# schema3.net
KiCad netlist of a schematic drawn in Altium Designer
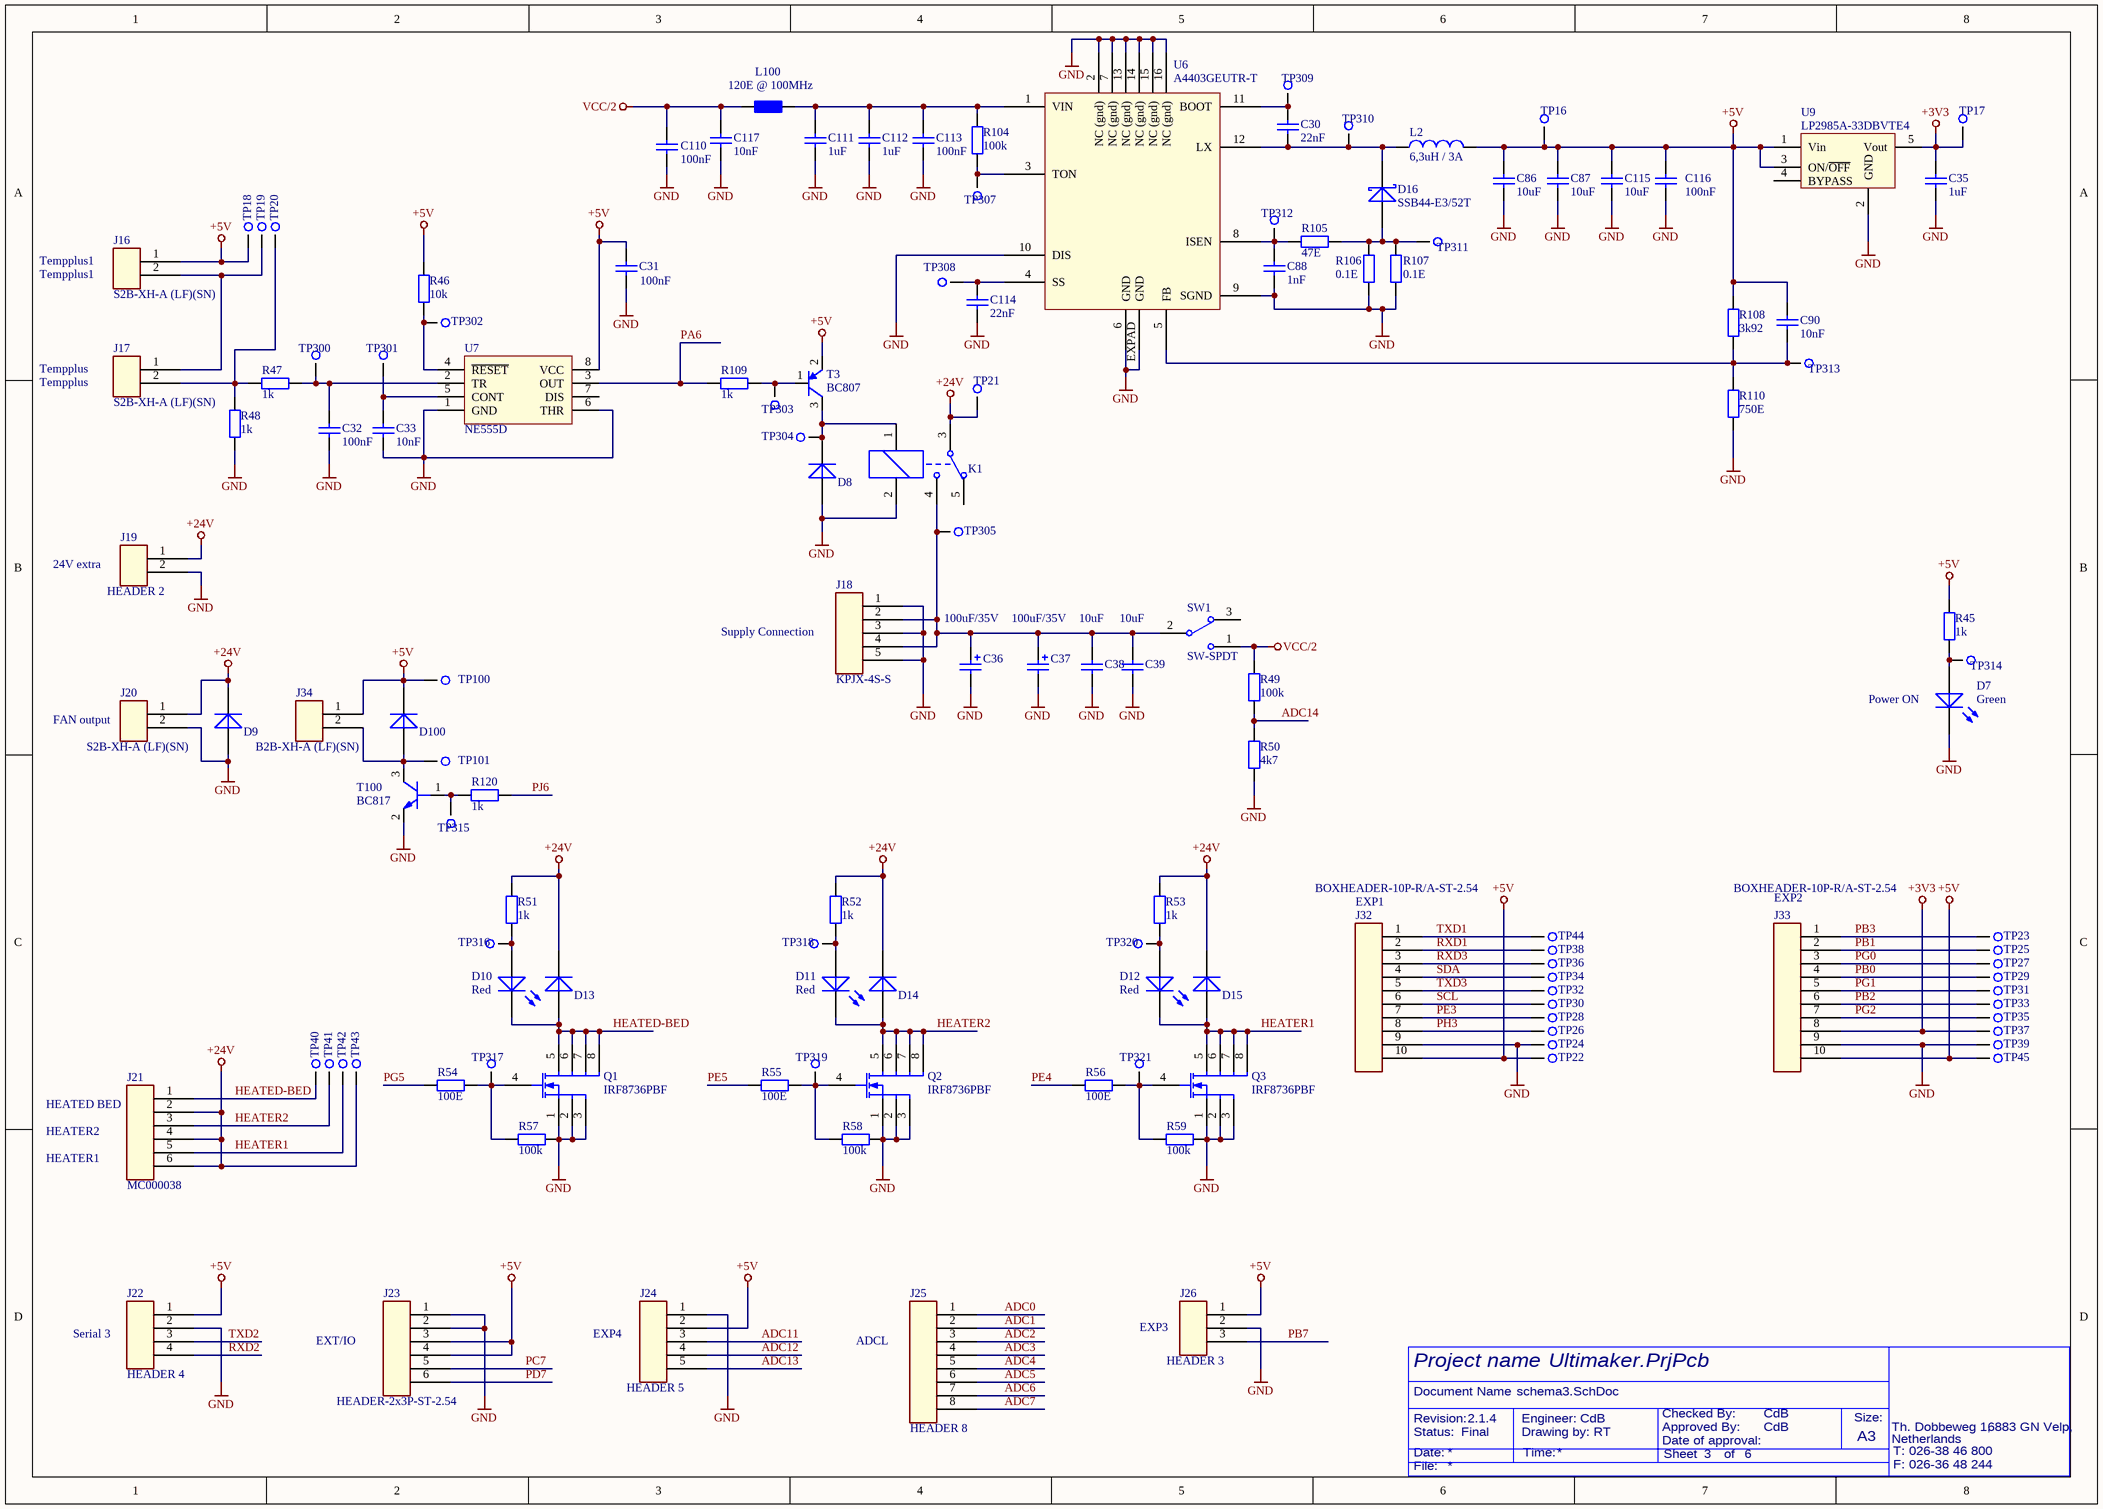
[diagram p0: schema3.SchDoc]

(export (version "E")
  (design (tool "Eeschema 10.0.6"))
  (components
    (comp (ref "C30")
      (value "22nF")
      (footprint "C0603")
      (description "RO X7R 22nF 10% 0603 50V CC0603KRX7R9BB223")
      (libsource (lib "Database_Faber") (part "Capacitor"))
    )
    (comp (ref "C31")
      (value "100nF")
      (footprint "C0603")
      (description "RO X7R 100nF 10% 50V 0603")
      (libsource (lib "Database_Faber") (part "Capacitor"))
    )
    (comp (ref "C32")
      (value "100nF")
      (footprint "C0603")
      (description "RO X7R 100nF 10% 50V 0603")
      (libsource (lib "Database_Faber") (part "Capacitor"))
    )
    (comp (ref "C33")
      (value "10nF")
      (footprint "C0603")
      (description "RO X7R 10nF 10% 50V 0603")
      (libsource (lib "Database_Faber") (part "Capacitor"))
    )
    (comp (ref "C35")
      (value "1uF")
      (footprint "C0603")
      (description "RO X5R 1uF 10% 10V 0603")
      (libsource (lib "Database_Faber") (part "Capacitor"))
    )
    (comp (ref "C36")
      (value "100uF/35V")
      (footprint "ELCO Case D")
      (description "RO ELCO 100uF 20% 35V CASE-D EEEFP PAN")
      (libsource (lib "Database_Faber") (part "Capacitor Polarity"))
    )
    (comp (ref "C37")
      (value "100uF/35V")
      (footprint "ELCO Case D")
      (description "RO ELCO 100uF 20% 35V CASE-D EEEFP PAN")
      (libsource (lib "Database_Faber") (part "Capacitor Polarity"))
    )
    (comp (ref "C38")
      (value "10uF")
      (footprint "C1206")
      (description "RO X5R 10UF 10% 35V 1206")
      (libsource (lib "Database_Faber") (part "Capacitor"))
    )
    (comp (ref "C39")
      (value "10uF")
      (footprint "C1206")
      (description "RO X5R 10UF 10% 35V 1206")
      (libsource (lib "Database_Faber") (part "Capacitor"))
    )
    (comp (ref "C86")
      (value "10uF")
      (footprint "C0805")
      (description "6R3R15X106KV4E - MLCC, 0805, X5R, 6.3V, 10UF")
      (fields (field (name "MFG") "JOHANSON DIELECTRICS"))
      (libsource (lib "Database_Faber") (part "Capacitor"))
    )
    (comp (ref "C87")
      (value "10uF")
      (footprint "C0805")
      (description "6R3R15X106KV4E - MLCC, 0805, X5R, 6.3V, 10UF")
      (fields (field (name "MFG") "JOHANSON DIELECTRICS"))
      (libsource (lib "Database_Faber") (part "Capacitor"))
    )
    (comp (ref "C88")
      (value "1nF")
      (footprint "C0603")
      (description "RO C0G 1nF 5% 50V 0603")
      (libsource (lib "Database_Faber") (part "Capacitor"))
    )
    (comp (ref "C90")
      (value "10nF")
      (footprint "C0603")
      (description "RO X7R 10nF 10% 50V 0603")
      (libsource (lib "Database_Faber") (part "Capacitor"))
    )
    (comp (ref "C110")
      (value "100nF")
      (footprint "Ultimaker:C0603")
      (description "RO X7R 100nF 10% 50V 0603")
      (libsource (lib "Database_Faber") (part "Capacitor"))
    )
    (comp (ref "C111")
      (value "1uF")
      (footprint "Ultimaker:C1206")
      (description "X7R 1uF 10% 50V 1206 GRM31")
      (libsource (lib "Ultimaker") (part "Capacitor_1_1"))
    )
    (comp (ref "C112")
      (value "1uF")
      (footprint "Ultimaker:C1206")
      (description "X7R 1uF 10% 50V 1206 GRM31")
      (libsource (lib "Ultimaker") (part "Capacitor_1_1"))
    )
    (comp (ref "C113")
      (value "100nF")
      (footprint "Ultimaker:C0603")
      (description "RO X7R 100nF 10% 50V 0603")
      (libsource (lib "Database_Faber") (part "Capacitor"))
    )
    (comp (ref "C114")
      (value "22nF")
      (footprint "Ultimaker:C0603")
      (description "RO X7R 22nF 10% 0603 50V CC0603KRX7R9BB223")
      (libsource (lib "Database_Faber") (part "Capacitor"))
    )
    (comp (ref "C115")
      (value "10uF")
      (footprint "Ultimaker:C0805")
      (description "6R3R15X106KV4E - MLCC, 0805, X5R, 6.3V, 10UF")
      (fields (field (name "MFG") "JOHANSON DIELECTRICS"))
      (libsource (lib "Database_Faber") (part "Capacitor"))
    )
    (comp (ref "C116")
      (value "100nF")
      (footprint "Ultimaker:C0603")
      (description "RO X7R 100nF 10% 50V 0603")
      (libsource (lib "Database_Faber") (part "Capacitor"))
    )
    (comp (ref "C117")
      (value "10nF")
      (footprint "Ultimaker:C0603")
      (description "RO X7R 10nF 10% 50V 0603")
      (libsource (lib "Database_Faber") (part "Capacitor"))
    )
    (comp (ref "D7")
      (value "Green")
      (footprint "LED0805-GREEN")
      (description "RO LED GROEN HSMG-C170 0805 AVAGO")
      (fields (field (name "MFG") "AVAGO"))
      (libsource (lib "Database_Faber") (part "LED"))
    )
    (comp (ref "D8")
      (value "S1G")
      (footprint "DO214AC (SMA)")
      (description "RO DIODE S1G DO-214AC")
      (libsource (lib "") (part "Diode_1"))
    )
    (comp (ref "D9")
      (value "S1G")
      (footprint "DO214AC (SMA)")
      (description "RO DIODE S1G DO-214AC")
      (libsource (lib "") (part "Diode_1"))
    )
    (comp (ref "D10")
      (value "Red")
      (footprint "LED0805-RED")
      (description "RO LED ROOD HSMH-C170 0805 AVAGO")
      (fields (field (name "MFG") "AVAGO"))
      (libsource (lib "Database_Faber") (part "LED"))
    )
    (comp (ref "D11")
      (value "Red")
      (footprint "LED0805-RED")
      (description "RO LED ROOD HSMH-C170 0805 AVAGO")
      (fields (field (name "MFG") "AVAGO"))
      (libsource (lib "Database_Faber") (part "LED"))
    )
    (comp (ref "D12")
      (value "Red")
      (footprint "LED0805-RED")
      (description "RO LED ROOD HSMH-C170 0805 AVAGO")
      (fields (field (name "MFG") "AVAGO"))
      (libsource (lib "Database_Faber") (part "LED"))
    )
    (comp (ref "D13")
      (value "S1G")
      (footprint "DO214AC (SMA)")
      (description "RO DIODE S1G DO-214AC")
      (libsource (lib "") (part "Diode_1"))
    )
    (comp (ref "D14")
      (value "S1G")
      (footprint "DO214AC (SMA)")
      (description "RO DIODE S1G DO-214AC")
      (libsource (lib "") (part "Diode_1"))
    )
    (comp (ref "D15")
      (value "S1G")
      (footprint "DO214AC (SMA)")
      (description "RO DIODE S1G DO-214AC")
      (libsource (lib "") (part "Diode_1"))
    )
    (comp (ref "D16")
      (value "SSB44-E3/52T")
      (footprint "DO214AA (SMB)")
      (description "RO DIODE SSB44-E3/52T SMB VISHAY")
      (fields (field (name "MFG") "VISHAY"))
      (libsource (lib "Database_Faber") (part "Schottky"))
    )
    (comp (ref "D100")
      (value "S1G")
      (footprint "Ultimaker:DO214AC (SMA)")
      (description "RO DIODE S1G DO-214AC")
      (libsource (lib "Database_Faber") (part "Diode"))
    )
    (comp (ref "J16")
      (value "S2B-XH-A (LF)(SN)")
      (footprint "S2B-XH-A (LF)(SN)")
      (description "RO CONN PR 2p HKS S2B-XH-A (LF)(SN) JST")
      (fields (field (name "MFG") "JST (JAPAN SOLDERLESS TERMINALS)"))
      (libsource (lib "Database_Faber") (part "HEADER 2"))
    )
    (comp (ref "J17")
      (value "S2B-XH-A (LF)(SN)")
      (footprint "S2B-XH-A (LF)(SN)")
      (description "RO CONN PR 2p HKS S2B-XH-A (LF)(SN) JST")
      (fields (field (name "MFG") "JST (JAPAN SOLDERLESS TERMINALS)"))
      (libsource (lib "Database_Faber") (part "HEADER 2"))
    )
    (comp (ref "J18")
      (value "KPJX-4S-S")
      (footprint "KPJX-4S-S")
      (description "RO CONN PR KPJX-4S-S KYCON")
      (fields (field (name "MFG") "KYCON"))
      (libsource (lib "Database_Faber") (part "HEADER 5"))
    )
    (comp (ref "J19")
      (value "HEADER 2")
      (footprint "HEADER-1x2P-ST-2.54")
      (description "HEADER-1x2P-ST-2.54")
      (libsource (lib "Database_Faber") (part "HEADER 2"))
    )
    (comp (ref "J20")
      (value "S2B-XH-A (LF)(SN)")
      (footprint "S2B-XH-A (LF)(SN)")
      (description "RO CONN PR 2p HKS S2B-XH-A (LF)(SN) JST")
      (fields (field (name "MFG") "JST (JAPAN SOLDERLESS TERMINALS)"))
      (libsource (lib "Database_Faber") (part "HEADER 2"))
    )
    (comp (ref "J21")
      (value "MC000038")
      (footprint "MC000038")
      (description "RO CONN PR 6p MC000038 MULTICOMP")
      (fields (field (name "MFG") "MULTICOMP"))
      (libsource (lib "Database_Faber") (part "HEADER 6"))
    )
    (comp (ref "J22")
      (value "HEADER 4")
      (footprint "HEADER-1x4P-ST-2.54")
      (description "HEADER-1x4P-ST-2.54")
      (libsource (lib "Database_Faber") (part "HEADER 4"))
    )
    (comp (ref "J23")
      (value "HEADER-2x3P-ST-2.54")
      (footprint "HEADER-2x3P-ST-2.54")
      (description "RO CONN PR HDR 2X3P H4B-06DS-0000 INT")
      (libsource (lib "Database_Faber") (part "HEADER 6"))
    )
    (comp (ref "J24")
      (value "HEADER 5")
      (footprint "HEADER-1x5P-ST-2.54")
      (description "HEADER-1x5P-ST-2.54")
      (libsource (lib "Database_Faber") (part "HEADER 5"))
    )
    (comp (ref "J25")
      (value "HEADER 8")
      (footprint "HEADER-1x8P-ST-2.54")
      (description "HEADER-1x8P-ST-2.54")
      (libsource (lib "Database_Faber") (part "HEADER 8"))
    )
    (comp (ref "J26")
      (value "HEADER 3")
      (footprint "HEADER-1x3P-ST-2.54")
      (description "HEADER-1x3P-ST-2.54")
      (libsource (lib "Database_Faber") (part "HEADER 3"))
    )
    (comp (ref "J32")
      (value "BOXHEADER-10P-R/A-ST-2.54")
      (footprint "BOXHEADER-10P-R/A-ST-2.54")
      (description "RO CONN PR HDR BOX 10p HKS 61201021721 WUERTH")
      (libsource (lib "Database_Faber") (part "HEADER 10"))
    )
    (comp (ref "J33")
      (value "BOXHEADER-10P-R/A-ST-2.54")
      (footprint "BOXHEADER-10P-R/A-ST-2.54")
      (description "RO CONN PR HDR BOX 10p HKS 61201021721 WUERTH")
      (libsource (lib "Database_Faber") (part "HEADER 10"))
    )
    (comp (ref "J34")
      (value "B2B-XH-A (LF)(SN)")
      (footprint "B2B-XH-A (LF)(SN)")
      (description "CONN PR 2p B2B-XH-A JST")
      (fields (field (name "MFG") "JST (JAPAN SOLDERLESS TERMINALS)"))
      (libsource (lib "Ultimaker") (part "HEADER 2_3"))
    )
    (comp (ref "K1")
      (value "Relay-SPDT")
      (footprint "HRS4-S")
      (description "RO REL 5V HRS4-S DC5V MULTICOMP")
      (fields (field (name "MFG") "MULTICOMP"))
      (libsource (lib "Database_Faber") (part "Relay-SPDT"))
    )
    (comp (ref "L2")
      (value "6,3uH / 3A")
      (footprint "NRS6045")
      (description "RO SPOEL 6,3uH 20% NRS6045T 6R3MMGK TAIYO YUDEN")
      (fields (field (name "MFG") "TAIYO YUDEN"))
      (libsource (lib "Database_Faber") (part "Inductor"))
    )
    (comp (ref "L100")
      (value "120E @ 100MHz")
      (footprint "Ultimaker:R0603")
      (description "FERRIET BLM18PG121SN1D 0603 MURATA")
      (fields (field (name "MFG") "Murata"))
      (libsource (lib "Ultimaker") (part "Ferriet Bead 120E"))
    )
    (comp (ref "Q1")
      (value "IRF8736PBF")
      (footprint "SOIC127P600X175-8N (SO8)")
      (description "IRF8736PBF - MOSFET, N SO-8")
      (fields (field (name "MFG") "INTERNATIONAL RECTIFIER"))
      (libsource (lib "Database_Faber") (part "MOSFET-N-SO8"))
    )
    (comp (ref "Q2")
      (value "IRF8736PBF")
      (footprint "SOIC127P600X175-8N (SO8)")
      (description "IRF8736PBF - MOSFET, N SO-8")
      (fields (field (name "MFG") "INTERNATIONAL RECTIFIER"))
      (libsource (lib "Database_Faber") (part "MOSFET-N-SO8"))
    )
    (comp (ref "Q3")
      (value "IRF8736PBF")
      (footprint "SOIC127P600X175-8N (SO8)")
      (description "IRF8736PBF - MOSFET, N SO-8")
      (fields (field (name "MFG") "INTERNATIONAL RECTIFIER"))
      (libsource (lib "Database_Faber") (part "MOSFET-N-SO8"))
    )
    (comp (ref "R45")
      (value "1k")
      (footprint "R0603")
      (description "RO RES 1k0 1% 0,1W  0603")
      (libsource (lib "Database_Faber") (part "Resistor"))
    )
    (comp (ref "R46")
      (value "10k")
      (footprint "R0603")
      (description "RO RES 10k0 1% 0,063W  0603")
      (libsource (lib "Database_Faber") (part "Resistor"))
    )
    (comp (ref "R47")
      (value "1k")
      (footprint "R0603")
      (description "RO RES 1k0 1% 0,1W  0603")
      (libsource (lib "") (part "Resistor_1"))
    )
    (comp (ref "R48")
      (value "1k")
      (footprint "R0603")
      (description "RO RES 1k0 1% 0,1W  0603")
      (libsource (lib "Database_Faber") (part "Resistor"))
    )
    (comp (ref "R49")
      (value "100k")
      (footprint "R0603")
      (description "RO RES 100k0 1% 0,063W  0603")
      (libsource (lib "Database_Faber") (part "Resistor"))
    )
    (comp (ref "R50")
      (value "4k7")
      (footprint "R0603")
      (description "RO RES 4k70 1% 0,063W  0603")
      (libsource (lib "Database_Faber") (part "Resistor"))
    )
    (comp (ref "R51")
      (value "1k")
      (footprint "R0603")
      (description "RO RES 1k0 1% 0,1W  0603")
      (libsource (lib "Database_Faber") (part "Resistor"))
    )
    (comp (ref "R52")
      (value "1k")
      (footprint "R0603")
      (description "RO RES 1k0 1% 0,1W  0603")
      (libsource (lib "Database_Faber") (part "Resistor"))
    )
    (comp (ref "R53")
      (value "1k")
      (footprint "R0603")
      (description "RO RES 1k0 1% 0,1W  0603")
      (libsource (lib "Database_Faber") (part "Resistor"))
    )
    (comp (ref "R54")
      (value "100E")
      (footprint "R0603")
      (description "RO RES 100E 1% 0,063W  0603")
      (libsource (lib "") (part "Resistor_1"))
    )
    (comp (ref "R55")
      (value "100E")
      (footprint "R0603")
      (description "RO RES 100E 1% 0,063W  0603")
      (libsource (lib "") (part "Resistor_1"))
    )
    (comp (ref "R56")
      (value "100E")
      (footprint "R0603")
      (description "RO RES 100E 1% 0,063W  0603")
      (libsource (lib "") (part "Resistor_1"))
    )
    (comp (ref "R57")
      (value "100k")
      (footprint "R0603")
      (description "RO RES 100k0 1% 0,063W  0603")
      (libsource (lib "") (part "Resistor_1"))
    )
    (comp (ref "R58")
      (value "100k")
      (footprint "R0603")
      (description "RO RES 100k0 1% 0,063W  0603")
      (libsource (lib "") (part "Resistor_1"))
    )
    (comp (ref "R59")
      (value "100k")
      (footprint "R0603")
      (description "RO RES 100k0 1% 0,063W  0603")
      (libsource (lib "") (part "Resistor_1"))
    )
    (comp (ref "R104")
      (value "100k")
      (footprint "R0603")
      (description "RO RES 100k0 1% 0,063W  0603")
      (libsource (lib "Database_Faber") (part "Resistor"))
    )
    (comp (ref "R105")
      (value "47E")
      (footprint "R0603")
      (description "RO RES 47E 1% 0,063W 0603")
      (libsource (lib "") (part "Resistor_1"))
    )
    (comp (ref "R106")
      (value "0.1E")
      (footprint "Ultimaker:R0805")
      (description "RES 0E10 1% 0,125W 0805")
      (libsource (lib "Database_Faber") (part "Resistor"))
    )
    (comp (ref "R107")
      (value "0.1E")
      (footprint "Ultimaker:R0805")
      (description "RES 0E10 1% 0,125W 0805")
      (libsource (lib "Database_Faber") (part "Resistor"))
    )
    (comp (ref "R108")
      (value "3k92")
      (footprint "R0603")
      (description "RO RES 3k92 1% 0.063W 0603")
      (libsource (lib "Database_Faber") (part "Resistor"))
    )
    (comp (ref "R109")
      (value "1k")
      (footprint "R0603")
      (description "RO RES 1k0 1% 0,1W  0603")
      (libsource (lib "") (part "Resistor_1"))
    )
    (comp (ref "R110")
      (value "750E")
      (footprint "R0603")
      (description "RO RES 750E 1% 0,063W 0603")
      (libsource (lib "Database_Faber") (part "Resistor"))
    )
    (comp (ref "R120")
      (value "1k")
      (footprint "Ultimaker:R0603")
      (description "RO RES 1k0 1% 0,1W  0603")
      (libsource (lib "") (part "Resistor_2"))
    )
    (comp (ref "SW1")
      (value "SW-SPDT")
      (footprint "RS 734-6918")
      (description "Rocker switch,SPDT,on-none-on,RA,snap-in")
      (fields (field (name "MFG") "RS Components"))
      (libsource (lib "Database_Faber") (part "SW-SPDT"))
    )
    (comp (ref "T3")
      (value "BC807")
      (footprint "SOT23")
      (description "RO TRANS BC807-40  SOT-23")
      (libsource (lib "Database_Faber") (part "Transistor PNP"))
    )
    (comp (ref "T100")
      (value "BC817")
      (footprint "Ultimaker:SOT23")
      (description "RO TRANS BC817-25  SOT-23")
      (libsource (lib "Database_Faber") (part "Transistor NPN"))
    )
    (comp (ref "TP16")
      (value "Testpoint")
      (footprint "Testpoint")
      (libsource (lib "Database_Faber") (part "Testpoint"))
    )
    (comp (ref "TP17")
      (value "Testpoint")
      (footprint "Testpoint")
      (libsource (lib "Database_Faber") (part "Testpoint"))
    )
    (comp (ref "TP18")
      (value "Testpoint")
      (footprint "Testpoint")
      (libsource (lib "Database_Faber") (part "Testpoint"))
    )
    (comp (ref "TP19")
      (value "Testpoint")
      (footprint "Testpoint")
      (libsource (lib "Database_Faber") (part "Testpoint"))
    )
    (comp (ref "TP20")
      (value "Testpoint")
      (footprint "Testpoint")
      (libsource (lib "Database_Faber") (part "Testpoint"))
    )
    (comp (ref "TP21")
      (value "Testpoint")
      (footprint "Testpoint")
      (libsource (lib "Database_Faber") (part "Testpoint"))
    )
    (comp (ref "TP22")
      (value "Testpoint")
      (footprint "Testpoint")
      (libsource (lib "Database_Faber") (part "Testpoint"))
    )
    (comp (ref "TP23")
      (value "Testpoint")
      (footprint "Testpoint")
      (libsource (lib "Database_Faber") (part "Testpoint"))
    )
    (comp (ref "TP24")
      (value "Testpoint")
      (footprint "Testpoint")
      (libsource (lib "Database_Faber") (part "Testpoint"))
    )
    (comp (ref "TP25")
      (value "Testpoint")
      (footprint "Testpoint")
      (libsource (lib "Database_Faber") (part "Testpoint"))
    )
    (comp (ref "TP26")
      (value "Testpoint")
      (footprint "Testpoint")
      (libsource (lib "Database_Faber") (part "Testpoint"))
    )
    (comp (ref "TP27")
      (value "Testpoint")
      (footprint "Testpoint")
      (libsource (lib "Database_Faber") (part "Testpoint"))
    )
    (comp (ref "TP28")
      (value "Testpoint")
      (footprint "Testpoint")
      (libsource (lib "Database_Faber") (part "Testpoint"))
    )
    (comp (ref "TP29")
      (value "Testpoint")
      (footprint "Testpoint")
      (libsource (lib "Database_Faber") (part "Testpoint"))
    )
    (comp (ref "TP30")
      (value "Testpoint")
      (footprint "Testpoint")
      (libsource (lib "Database_Faber") (part "Testpoint"))
    )
    (comp (ref "TP31")
      (value "Testpoint")
      (footprint "Testpoint")
      (libsource (lib "Database_Faber") (part "Testpoint"))
    )
    (comp (ref "TP32")
      (value "Testpoint")
      (footprint "Testpoint")
      (libsource (lib "Database_Faber") (part "Testpoint"))
    )
    (comp (ref "TP33")
      (value "Testpoint")
      (footprint "Testpoint")
      (libsource (lib "Database_Faber") (part "Testpoint"))
    )
    (comp (ref "TP34")
      (value "Testpoint")
      (footprint "Testpoint")
      (libsource (lib "Database_Faber") (part "Testpoint"))
    )
    (comp (ref "TP35")
      (value "Testpoint")
      (footprint "Testpoint")
      (libsource (lib "Database_Faber") (part "Testpoint"))
    )
    (comp (ref "TP36")
      (value "Testpoint")
      (footprint "Testpoint")
      (libsource (lib "Database_Faber") (part "Testpoint"))
    )
    (comp (ref "TP37")
      (value "Testpoint")
      (footprint "Testpoint")
      (libsource (lib "Database_Faber") (part "Testpoint"))
    )
    (comp (ref "TP38")
      (value "Testpoint")
      (footprint "Testpoint")
      (libsource (lib "Database_Faber") (part "Testpoint"))
    )
    (comp (ref "TP39")
      (value "Testpoint")
      (footprint "Testpoint")
      (libsource (lib "Database_Faber") (part "Testpoint"))
    )
    (comp (ref "TP40")
      (value "Testpoint")
      (footprint "Testpoint")
      (libsource (lib "Database_Faber") (part "Testpoint"))
    )
    (comp (ref "TP41")
      (value "Testpoint")
      (footprint "Testpoint")
      (libsource (lib "Database_Faber") (part "Testpoint"))
    )
    (comp (ref "TP42")
      (value "Testpoint")
      (footprint "Testpoint")
      (libsource (lib "Database_Faber") (part "Testpoint"))
    )
    (comp (ref "TP43")
      (value "Testpoint")
      (footprint "Testpoint")
      (libsource (lib "Database_Faber") (part "Testpoint"))
    )
    (comp (ref "TP44")
      (value "Testpoint")
      (footprint "Testpoint")
      (libsource (lib "Database_Faber") (part "Testpoint"))
    )
    (comp (ref "TP45")
      (value "Testpoint")
      (footprint "Testpoint")
      (libsource (lib "Database_Faber") (part "Testpoint"))
    )
    (comp (ref "TP100")
      (value "Testpoint")
      (footprint "Ultimaker:Testpoint")
      (libsource (lib "Database_Faber") (part "Testpoint"))
    )
    (comp (ref "TP101")
      (value "Testpoint")
      (footprint "Ultimaker:Testpoint")
      (libsource (lib "Database_Faber") (part "Testpoint"))
    )
    (comp (ref "TP300")
      (value "Testpoint 1.6mm")
      (footprint "Testpoint 1.6mm")
      (libsource (lib "Ultimaker") (part "Testpoint 1.6mm"))
    )
    (comp (ref "TP301")
      (value "Testpoint 1.6mm")
      (footprint "Testpoint 1.6mm")
      (libsource (lib "Ultimaker") (part "Testpoint 1.6mm"))
    )
    (comp (ref "TP302")
      (value "Testpoint 1.6mm")
      (footprint "Testpoint 1.6mm")
      (libsource (lib "Ultimaker") (part "Testpoint 1.6mm"))
    )
    (comp (ref "TP303")
      (value "Testpoint 1.6mm")
      (footprint "Testpoint 1.6mm")
      (libsource (lib "Ultimaker") (part "Testpoint 1.6mm"))
    )
    (comp (ref "TP304")
      (value "Testpoint 1.6mm")
      (footprint "Testpoint 1.6mm")
      (libsource (lib "Ultimaker") (part "Testpoint 1.6mm"))
    )
    (comp (ref "TP305")
      (value "Testpoint 1.6mm")
      (footprint "Testpoint 1.6mm")
      (libsource (lib "Ultimaker") (part "Testpoint 1.6mm"))
    )
    (comp (ref "TP307")
      (value "Testpoint 1.6mm")
      (footprint "Testpoint 1.6mm")
      (libsource (lib "Ultimaker") (part "Testpoint 1.6mm"))
    )
    (comp (ref "TP308")
      (value "Testpoint 1.6mm")
      (footprint "Testpoint 1.6mm")
      (libsource (lib "Ultimaker") (part "Testpoint 1.6mm"))
    )
    (comp (ref "TP309")
      (value "Testpoint 1.6mm")
      (footprint "Testpoint 1.6mm")
      (libsource (lib "Ultimaker") (part "Testpoint 1.6mm"))
    )
    (comp (ref "TP310")
      (value "Testpoint 1.6mm")
      (footprint "Testpoint 1.6mm")
      (libsource (lib "Ultimaker") (part "Testpoint 1.6mm"))
    )
    (comp (ref "TP311")
      (value "Testpoint 1.6mm")
      (footprint "Testpoint 1.6mm")
      (libsource (lib "Ultimaker") (part "Testpoint 1.6mm"))
    )
    (comp (ref "TP312")
      (value "Testpoint 1.6mm")
      (footprint "Testpoint 1.6mm")
      (libsource (lib "Ultimaker") (part "Testpoint 1.6mm"))
    )
    (comp (ref "TP313")
      (value "Testpoint 1.6mm")
      (footprint "Testpoint 1.6mm")
      (libsource (lib "Ultimaker") (part "Testpoint 1.6mm"))
    )
    (comp (ref "TP314")
      (value "Testpoint 1.6mm")
      (footprint "Testpoint 1.6mm")
      (libsource (lib "Ultimaker") (part "Testpoint 1.6mm"))
    )
    (comp (ref "TP315")
      (value "Testpoint 1.6mm")
      (footprint "Testpoint 1.6mm")
      (libsource (lib "Ultimaker") (part "Testpoint 1.6mm"))
    )
    (comp (ref "TP316")
      (value "Testpoint 1.6mm")
      (footprint "Testpoint 1.6mm")
      (libsource (lib "Ultimaker") (part "Testpoint 1.6mm"))
    )
    (comp (ref "TP317")
      (value "Testpoint 1.6mm")
      (footprint "Testpoint 1.6mm")
      (libsource (lib "Ultimaker") (part "Testpoint 1.6mm"))
    )
    (comp (ref "TP318")
      (value "Testpoint 1.6mm")
      (footprint "Testpoint 1.6mm")
      (libsource (lib "Ultimaker") (part "Testpoint 1.6mm"))
    )
    (comp (ref "TP319")
      (value "Testpoint 1.6mm")
      (footprint "Testpoint 1.6mm")
      (libsource (lib "Ultimaker") (part "Testpoint 1.6mm"))
    )
    (comp (ref "TP320")
      (value "Testpoint 1.6mm")
      (footprint "Testpoint 1.6mm")
      (libsource (lib "Ultimaker") (part "Testpoint 1.6mm"))
    )
    (comp (ref "TP321")
      (value "Testpoint 1.6mm")
      (footprint "Testpoint 1.6mm")
      (libsource (lib "Ultimaker") (part "Testpoint 1.6mm"))
    )
    (comp (ref "U6")
      (value "A4403GEUTR-T")
      (footprint "QFN65P400X400X80-16N-EX")
      (description "RO IC A4403GEUTR-T QFN-16 ALLEGRO")
      (fields (field (name "MFG") "Allegro"))
      (libsource (lib "Database_Faber") (part "A4403GEUTR-T"))
    )
    (comp (ref "U7")
      (value "NE555D")
      (footprint "SOIC127P600X175-8N (SO8)")
      (description "RO IC NE555D SO-08 TI")
      (fields (field (name "MFG") "Texas Instruments"))
      (libsource (lib "Database_Faber") (part "NE555D"))
    )
    (comp (ref "U9")
      (value "LP2985A-33DBVTE4")
      (footprint "SOT95P280X145-5N (SOT23-5L)")
      (description "RO STABI LP2985A-33DBVTE4 SOT-23-5 TI")
      (fields (field (name "MFG") "Texas Instruments"))
      (libsource (lib "Database_Faber") (part "LP2985A-33DBVTE4"))
    )
  )
  (nets
    (net (code "1") (name "+3V3") (class "Default")
      (node (ref "C35") (pin "2") (pinfunction "2_2") (pintype "passive"))
      (node (ref "J33") (pin "8") (pinfunction "8_8") (pintype "passive"))
      (node (ref "TP17") (pin "1") (pinfunction "1_1") (pintype "passive"))
      (node (ref "TP37") (pin "1") (pinfunction "1_1") (pintype "passive"))
      (node (ref "U9") (pin "5") (pinfunction "Vout_5") (pintype "passive"))
    )
    (net (code "2") (name "+5V") (class "Default")
      (node (ref "C115") (pin "2") (pinfunction "2_2") (pintype "passive"))
      (node (ref "C116") (pin "2") (pinfunction "2_2") (pintype "passive"))
      (node (ref "C31") (pin "2") (pinfunction "2_2") (pintype "passive"))
      (node (ref "C86") (pin "2") (pinfunction "2_2") (pintype "passive"))
      (node (ref "C87") (pin "2") (pinfunction "2_2") (pintype "passive"))
      (node (ref "C90") (pin "2") (pinfunction "2_2") (pintype "passive"))
      (node (ref "D100") (pin "2") (pinfunction "K_2") (pintype "passive"))
      (node (ref "J16") (pin "1") (pinfunction "1_1") (pintype "passive"))
      (node (ref "J22") (pin "1") (pinfunction "1_1") (pintype "passive"))
      (node (ref "J23") (pin "3") (pinfunction "3_3") (pintype "passive"))
      (node (ref "J23") (pin "4") (pinfunction "4_4") (pintype "passive"))
      (node (ref "J24") (pin "2") (pinfunction "2_2") (pintype "passive"))
      (node (ref "J26") (pin "1") (pinfunction "1_1") (pintype "passive"))
      (node (ref "J32") (pin "10") (pinfunction "10_10") (pintype "passive"))
      (node (ref "J33") (pin "10") (pinfunction "10_10") (pintype "passive"))
      (node (ref "J34") (pin "1") (pinfunction "1_1") (pintype "passive"))
      (node (ref "L2") (pin "2") (pinfunction "2_2") (pintype "passive"))
      (node (ref "R108") (pin "2") (pinfunction "2_2") (pintype "passive"))
      (node (ref "R45") (pin "2") (pinfunction "2_2") (pintype "passive"))
      (node (ref "R46") (pin "2") (pinfunction "2_2") (pintype "passive"))
      (node (ref "T3") (pin "2") (pinfunction "E_2") (pintype "passive"))
      (node (ref "TP100") (pin "1") (pinfunction "1_1") (pintype "passive"))
      (node (ref "TP16") (pin "1") (pinfunction "1_1") (pintype "passive"))
      (node (ref "TP18") (pin "1") (pinfunction "1_1") (pintype "passive"))
      (node (ref "TP22") (pin "1") (pinfunction "1_1") (pintype "passive"))
      (node (ref "TP45") (pin "1") (pinfunction "1_1") (pintype "passive"))
      (node (ref "U7") (pin "8") (pinfunction "VCC_8") (pintype "passive"))
      (node (ref "U9") (pin "1") (pinfunction "Vin_1") (pintype "passive"))
      (node (ref "U9") (pin "3") (pinfunction "ON/~{OFF}_3") (pintype "passive"))
    )
    (net (code "3") (name "+24V") (class "Default")
      (node (ref "D13") (pin "2") (pinfunction "K_2") (pintype "passive"))
      (node (ref "D14") (pin "2") (pinfunction "K_2") (pintype "passive"))
      (node (ref "D15") (pin "2") (pinfunction "K_2") (pintype "passive"))
      (node (ref "D9") (pin "2") (pinfunction "K_2") (pintype "passive"))
      (node (ref "J19") (pin "1") (pinfunction "1_1") (pintype "passive"))
      (node (ref "J20") (pin "1") (pinfunction "1_1") (pintype "passive"))
      (node (ref "J21") (pin "2") (pinfunction "2_2") (pintype "passive"))
      (node (ref "J21") (pin "4") (pinfunction "4_4") (pintype "passive"))
      (node (ref "J21") (pin "6") (pinfunction "6_6") (pintype "passive"))
      (node (ref "K1") (pin "3") (pinfunction "3_3") (pintype "passive"))
      (node (ref "R51") (pin "2") (pinfunction "2_2") (pintype "passive"))
      (node (ref "R52") (pin "2") (pinfunction "2_2") (pintype "passive"))
      (node (ref "R53") (pin "2") (pinfunction "2_2") (pintype "passive"))
      (node (ref "TP21") (pin "1") (pinfunction "1_1") (pintype "passive"))
      (node (ref "TP43") (pin "1") (pinfunction "1_1") (pintype "passive"))
    )
    (net (code "4") (name "/ADC0") (class "Default")
      (node (ref "J25") (pin "1") (pinfunction "1_1") (pintype "passive"))
    )
    (net (code "5") (name "/ADC1") (class "Default")
      (node (ref "J25") (pin "2") (pinfunction "2_2") (pintype "passive"))
    )
    (net (code "6") (name "/ADC2") (class "Default")
      (node (ref "J25") (pin "3") (pinfunction "3_3") (pintype "passive"))
    )
    (net (code "7") (name "/ADC3") (class "Default")
      (node (ref "J25") (pin "4") (pinfunction "4_4") (pintype "passive"))
    )
    (net (code "8") (name "/ADC4") (class "Default")
      (node (ref "J25") (pin "5") (pinfunction "5_5") (pintype "passive"))
    )
    (net (code "9") (name "/ADC5") (class "Default")
      (node (ref "J25") (pin "6") (pinfunction "6_6") (pintype "passive"))
    )
    (net (code "10") (name "/ADC6") (class "Default")
      (node (ref "J25") (pin "7") (pinfunction "7_7") (pintype "passive"))
    )
    (net (code "11") (name "/ADC7") (class "Default")
      (node (ref "J25") (pin "8") (pinfunction "8_8") (pintype "passive"))
    )
    (net (code "12") (name "/ADC11") (class "Default")
      (node (ref "J24") (pin "3") (pinfunction "3_3") (pintype "passive"))
    )
    (net (code "13") (name "/ADC12") (class "Default")
      (node (ref "J24") (pin "4") (pinfunction "4_4") (pintype "passive"))
    )
    (net (code "14") (name "/ADC13") (class "Default")
      (node (ref "J24") (pin "5") (pinfunction "5_5") (pintype "passive"))
    )
    (net (code "15") (name "/ADC14") (class "Default")
      (node (ref "R49") (pin "1") (pinfunction "1_1") (pintype "passive"))
      (node (ref "R50") (pin "2") (pinfunction "2_2") (pintype "passive"))
    )
    (net (code "16") (name "/HEATED-BED") (class "Default")
      (node (ref "D10") (pin "2") (pinfunction "K_2") (pintype "passive"))
      (node (ref "D13") (pin "1") (pinfunction "A_1") (pintype "passive"))
      (node (ref "J21") (pin "1") (pinfunction "1_1") (pintype "passive"))
      (node (ref "Q1") (pin "5") (pinfunction "D_5") (pintype "passive"))
      (node (ref "Q1") (pin "6") (pinfunction "D_6") (pintype "passive"))
      (node (ref "Q1") (pin "7") (pinfunction "D_7") (pintype "passive"))
      (node (ref "Q1") (pin "8") (pinfunction "D_8") (pintype "passive"))
      (node (ref "TP40") (pin "1") (pinfunction "1_1") (pintype "passive"))
    )
    (net (code "17") (name "/HEATER1") (class "Default")
      (node (ref "D12") (pin "2") (pinfunction "K_2") (pintype "passive"))
      (node (ref "D15") (pin "1") (pinfunction "A_1") (pintype "passive"))
      (node (ref "J21") (pin "5") (pinfunction "5_5") (pintype "passive"))
      (node (ref "Q3") (pin "5") (pinfunction "D_5") (pintype "passive"))
      (node (ref "Q3") (pin "6") (pinfunction "D_6") (pintype "passive"))
      (node (ref "Q3") (pin "7") (pinfunction "D_7") (pintype "passive"))
      (node (ref "Q3") (pin "8") (pinfunction "D_8") (pintype "passive"))
      (node (ref "TP42") (pin "1") (pinfunction "1_1") (pintype "passive"))
    )
    (net (code "18") (name "/HEATER2") (class "Default")
      (node (ref "D11") (pin "2") (pinfunction "K_2") (pintype "passive"))
      (node (ref "D14") (pin "1") (pinfunction "A_1") (pintype "passive"))
      (node (ref "J21") (pin "3") (pinfunction "3_3") (pintype "passive"))
      (node (ref "Q2") (pin "5") (pinfunction "D_5") (pintype "passive"))
      (node (ref "Q2") (pin "6") (pinfunction "D_6") (pintype "passive"))
      (node (ref "Q2") (pin "7") (pinfunction "D_7") (pintype "passive"))
      (node (ref "Q2") (pin "8") (pinfunction "D_8") (pintype "passive"))
      (node (ref "TP41") (pin "1") (pinfunction "1_1") (pintype "passive"))
    )
    (net (code "19") (name "/PA6") (class "Default")
      (node (ref "R109") (pin "1") (pinfunction "1_1") (pintype "passive"))
      (node (ref "U7") (pin "3") (pinfunction "OUT_3") (pintype "passive"))
    )
    (net (code "20") (name "/PB0") (class "Default")
      (node (ref "J33") (pin "4") (pinfunction "4_4") (pintype "passive"))
      (node (ref "TP29") (pin "1") (pinfunction "1_1") (pintype "passive"))
    )
    (net (code "21") (name "/PB1") (class "Default")
      (node (ref "J33") (pin "2") (pinfunction "2_2") (pintype "passive"))
      (node (ref "TP25") (pin "1") (pinfunction "1_1") (pintype "passive"))
    )
    (net (code "22") (name "/PB2") (class "Default")
      (node (ref "J33") (pin "6") (pinfunction "6_6") (pintype "passive"))
      (node (ref "TP33") (pin "1") (pinfunction "1_1") (pintype "passive"))
    )
    (net (code "23") (name "/PB3") (class "Default")
      (node (ref "J33") (pin "1") (pinfunction "1_1") (pintype "passive"))
      (node (ref "TP23") (pin "1") (pinfunction "1_1") (pintype "passive"))
    )
    (net (code "24") (name "/PB7") (class "Default")
      (node (ref "J26") (pin "3") (pinfunction "3_3") (pintype "passive"))
    )
    (net (code "25") (name "/PC7") (class "Default")
      (node (ref "J23") (pin "5") (pinfunction "5_5") (pintype "passive"))
    )
    (net (code "26") (name "/PD7") (class "Default")
      (node (ref "J23") (pin "6") (pinfunction "6_6") (pintype "passive"))
    )
    (net (code "27") (name "/PE3") (class "Default")
      (node (ref "J32") (pin "7") (pinfunction "7_7") (pintype "passive"))
      (node (ref "TP28") (pin "1") (pinfunction "1_1") (pintype "passive"))
    )
    (net (code "28") (name "/PE4") (class "Default")
      (node (ref "R56") (pin "1") (pinfunction "1_1") (pintype "passive"))
    )
    (net (code "29") (name "/PE5") (class "Default")
      (node (ref "R55") (pin "1") (pinfunction "1_1") (pintype "passive"))
    )
    (net (code "30") (name "/PG0") (class "Default")
      (node (ref "J33") (pin "3") (pinfunction "3_3") (pintype "passive"))
      (node (ref "TP27") (pin "1") (pinfunction "1_1") (pintype "passive"))
    )
    (net (code "31") (name "/PG1") (class "Default")
      (node (ref "J33") (pin "5") (pinfunction "5_5") (pintype "passive"))
      (node (ref "TP31") (pin "1") (pinfunction "1_1") (pintype "passive"))
    )
    (net (code "32") (name "/PG2") (class "Default")
      (node (ref "J33") (pin "7") (pinfunction "7_7") (pintype "passive"))
      (node (ref "TP35") (pin "1") (pinfunction "1_1") (pintype "passive"))
    )
    (net (code "33") (name "/PG5") (class "Default")
      (node (ref "R54") (pin "1") (pinfunction "1_1") (pintype "passive"))
    )
    (net (code "34") (name "/PH3") (class "Default")
      (node (ref "J32") (pin "8") (pinfunction "8_8") (pintype "passive"))
      (node (ref "TP26") (pin "1") (pinfunction "1_1") (pintype "passive"))
    )
    (net (code "35") (name "/PJ6") (class "Default")
      (node (ref "R120") (pin "1") (pinfunction "1_1") (pintype "passive"))
    )
    (net (code "36") (name "/RXD1") (class "Default")
      (node (ref "J32") (pin "2") (pinfunction "2_2") (pintype "passive"))
      (node (ref "TP38") (pin "1") (pinfunction "1_1") (pintype "passive"))
    )
    (net (code "37") (name "/RXD2") (class "Default")
      (node (ref "J22") (pin "4") (pinfunction "4_4") (pintype "passive"))
    )
    (net (code "38") (name "/RXD3") (class "Default")
      (node (ref "J32") (pin "3") (pinfunction "3_3") (pintype "passive"))
      (node (ref "TP36") (pin "1") (pinfunction "1_1") (pintype "passive"))
    )
    (net (code "39") (name "/SCL") (class "Default")
      (node (ref "J32") (pin "6") (pinfunction "6_6") (pintype "passive"))
      (node (ref "TP30") (pin "1") (pinfunction "1_1") (pintype "passive"))
    )
    (net (code "40") (name "/SDA") (class "Default")
      (node (ref "J32") (pin "4") (pinfunction "4_4") (pintype "passive"))
      (node (ref "TP34") (pin "1") (pinfunction "1_1") (pintype "passive"))
    )
    (net (code "41") (name "/TXD1") (class "Default")
      (node (ref "J32") (pin "1") (pinfunction "1_1") (pintype "passive"))
      (node (ref "TP44") (pin "1") (pinfunction "1_1") (pintype "passive"))
    )
    (net (code "42") (name "/TXD2") (class "Default")
      (node (ref "J22") (pin "3") (pinfunction "3_3") (pintype "passive"))
    )
    (net (code "43") (name "/TXD3") (class "Default")
      (node (ref "J32") (pin "5") (pinfunction "5_5") (pintype "passive"))
      (node (ref "TP32") (pin "1") (pinfunction "1_1") (pintype "passive"))
    )
    (net (code "44") (name "GND") (class "Default")
      (node (ref "C110") (pin "1") (pinfunction "1_1") (pintype "passive"))
      (node (ref "C111") (pin "1") (pinfunction "1_1") (pintype "passive"))
      (node (ref "C112") (pin "1") (pinfunction "1_1") (pintype "passive"))
      (node (ref "C113") (pin "1") (pinfunction "1_1") (pintype "passive"))
      (node (ref "C114") (pin "1") (pinfunction "1_1") (pintype "passive"))
      (node (ref "C115") (pin "1") (pinfunction "1_1") (pintype "passive"))
      (node (ref "C116") (pin "1") (pinfunction "1_1") (pintype "passive"))
      (node (ref "C117") (pin "1") (pinfunction "1_1") (pintype "passive"))
      (node (ref "C31") (pin "1") (pinfunction "1_1") (pintype "passive"))
      (node (ref "C32") (pin "1") (pinfunction "1_1") (pintype "passive"))
      (node (ref "C33") (pin "1") (pinfunction "1_1") (pintype "passive"))
      (node (ref "C35") (pin "1") (pinfunction "1_1") (pintype "passive"))
      (node (ref "C36") (pin "2") (pinfunction "2_2") (pintype "passive"))
      (node (ref "C37") (pin "2") (pinfunction "2_2") (pintype "passive"))
      (node (ref "C38") (pin "1") (pinfunction "1_1") (pintype "passive"))
      (node (ref "C39") (pin "1") (pinfunction "1_1") (pintype "passive"))
      (node (ref "C86") (pin "1") (pinfunction "1_1") (pintype "passive"))
      (node (ref "C87") (pin "1") (pinfunction "1_1") (pintype "passive"))
      (node (ref "C88") (pin "1") (pinfunction "1_1") (pintype "passive"))
      (node (ref "D7") (pin "2") (pinfunction "K_2") (pintype "passive"))
      (node (ref "D8") (pin "1") (pinfunction "A_1") (pintype "passive"))
      (node (ref "D9") (pin "1") (pinfunction "A_1") (pintype "passive"))
      (node (ref "J18") (pin "1") (pinfunction "1_1") (pintype "passive"))
      (node (ref "J18") (pin "3") (pinfunction "3_3") (pintype "passive"))
      (node (ref "J18") (pin "5") (pinfunction "5_5") (pintype "passive"))
      (node (ref "J19") (pin "2") (pinfunction "2_2") (pintype "passive"))
      (node (ref "J20") (pin "2") (pinfunction "2_2") (pintype "passive"))
      (node (ref "J22") (pin "2") (pinfunction "2_2") (pintype "passive"))
      (node (ref "J23") (pin "1") (pinfunction "1_1") (pintype "passive"))
      (node (ref "J23") (pin "2") (pinfunction "2_2") (pintype "passive"))
      (node (ref "J24") (pin "1") (pinfunction "1_1") (pintype "passive"))
      (node (ref "J26") (pin "2") (pinfunction "2_2") (pintype "passive"))
      (node (ref "J32") (pin "9") (pinfunction "9_9") (pintype "passive"))
      (node (ref "J33") (pin "9") (pinfunction "9_9") (pintype "passive"))
      (node (ref "K1") (pin "2") (pinfunction "2_2") (pintype "passive"))
      (node (ref "Q1") (pin "1") (pinfunction "S_1") (pintype "passive"))
      (node (ref "Q1") (pin "2") (pinfunction "S_2") (pintype "passive"))
      (node (ref "Q1") (pin "3") (pinfunction "S_3") (pintype "passive"))
      (node (ref "Q2") (pin "1") (pinfunction "S_1") (pintype "passive"))
      (node (ref "Q2") (pin "2") (pinfunction "S_2") (pintype "passive"))
      (node (ref "Q2") (pin "3") (pinfunction "S_3") (pintype "passive"))
      (node (ref "Q3") (pin "1") (pinfunction "S_1") (pintype "passive"))
      (node (ref "Q3") (pin "2") (pinfunction "S_2") (pintype "passive"))
      (node (ref "Q3") (pin "3") (pinfunction "S_3") (pintype "passive"))
      (node (ref "R106") (pin "1") (pinfunction "1_1") (pintype "passive"))
      (node (ref "R107") (pin "1") (pinfunction "1_1") (pintype "passive"))
      (node (ref "R110") (pin "1") (pinfunction "1_1") (pintype "passive"))
      (node (ref "R48") (pin "1") (pinfunction "1_1") (pintype "passive"))
      (node (ref "R50") (pin "1") (pinfunction "1_1") (pintype "passive"))
      (node (ref "R57") (pin "2") (pinfunction "2_2") (pintype "passive"))
      (node (ref "R58") (pin "2") (pinfunction "2_2") (pintype "passive"))
      (node (ref "R59") (pin "2") (pinfunction "2_2") (pintype "passive"))
      (node (ref "T100") (pin "2") (pinfunction "EMITTER_2") (pintype "passive"))
      (node (ref "TP24") (pin "1") (pinfunction "1_1") (pintype "passive"))
      (node (ref "TP39") (pin "1") (pinfunction "1_1") (pintype "passive"))
      (node (ref "U6") (pin "10") (pinfunction "DIS_10") (pintype "passive"))
      (node (ref "U6") (pin "13") (pinfunction "NC_(gnd)_13") (pintype "passive"))
      (node (ref "U6") (pin "14") (pinfunction "NC_(gnd)_14") (pintype "passive"))
      (node (ref "U6") (pin "15") (pinfunction "NC_(gnd)_15") (pintype "passive"))
      (node (ref "U6") (pin "16") (pinfunction "NC_(gnd)_16") (pintype "passive"))
      (node (ref "U6") (pin "2") (pinfunction "NC_(gnd)_2") (pintype "passive"))
      (node (ref "U6") (pin "6") (pinfunction "GND_6") (pintype "passive"))
      (node (ref "U6") (pin "7") (pinfunction "NC_(gnd)_7") (pintype "passive"))
      (node (ref "U6") (pin "9") (pinfunction "SGND_9") (pintype "passive"))
      (node (ref "U6") (pin "EXPAD") (pinfunction "GND_EXPAD") (pintype "passive"))
      (node (ref "U7") (pin "1") (pinfunction "GND_1") (pintype "passive"))
      (node (ref "U7") (pin "6") (pinfunction "THR_6") (pintype "passive"))
      (node (ref "U9") (pin "2") (pinfunction "GND_2") (pintype "passive"))
    )
    (net (code "45") (name "Net-(C36-Pad1)") (class "Default")
      (node (ref "C36") (pin "1") (pinfunction "1_1") (pintype "passive"))
      (node (ref "C37") (pin "1") (pinfunction "1_1") (pintype "passive"))
      (node (ref "C38") (pin "2") (pinfunction "2_2") (pintype "passive"))
      (node (ref "C39") (pin "2") (pinfunction "2_2") (pintype "passive"))
      (node (ref "J18") (pin "2") (pinfunction "2_2") (pintype "passive"))
      (node (ref "J18") (pin "4") (pinfunction "4_4") (pintype "passive"))
      (node (ref "K1") (pin "4") (pinfunction "4_4") (pintype "passive"))
      (node (ref "SW1") (pin "2") (pinfunction "2_2") (pintype "passive"))
      (node (ref "TP305") (pin "1") (pinfunction "1_1") (pintype "passive"))
    )
    (net (code "46") (name "Net-(D7-A)") (class "Default")
      (node (ref "D7") (pin "1") (pinfunction "A_1") (pintype "passive"))
      (node (ref "R45") (pin "1") (pinfunction "1_1") (pintype "passive"))
      (node (ref "TP314") (pin "1") (pinfunction "1_1") (pintype "passive"))
    )
    (net (code "47") (name "Net-(D8-K)") (class "Default")
      (node (ref "D8") (pin "2") (pinfunction "K_2") (pintype "passive"))
      (node (ref "K1") (pin "1") (pinfunction "1_1") (pintype "passive"))
      (node (ref "T3") (pin "3") (pinfunction "C_3") (pintype "passive"))
      (node (ref "TP304") (pin "1") (pinfunction "1_1") (pintype "passive"))
    )
    (net (code "48") (name "Net-(D10-A)") (class "Default")
      (node (ref "D10") (pin "1") (pinfunction "A_1") (pintype "passive"))
      (node (ref "R51") (pin "1") (pinfunction "1_1") (pintype "passive"))
      (node (ref "TP316") (pin "1") (pinfunction "1_1") (pintype "passive"))
    )
    (net (code "49") (name "Net-(D11-A)") (class "Default")
      (node (ref "D11") (pin "1") (pinfunction "A_1") (pintype "passive"))
      (node (ref "R52") (pin "1") (pinfunction "1_1") (pintype "passive"))
      (node (ref "TP318") (pin "1") (pinfunction "1_1") (pintype "passive"))
    )
    (net (code "50") (name "Net-(D12-A)") (class "Default")
      (node (ref "D12") (pin "1") (pinfunction "A_1") (pintype "passive"))
      (node (ref "R53") (pin "1") (pinfunction "1_1") (pintype "passive"))
      (node (ref "TP320") (pin "1") (pinfunction "1_1") (pintype "passive"))
    )
    (net (code "51") (name "Net-(D16-A)") (class "Default")
      (node (ref "D16") (pin "1") (pinfunction "A_1") (pintype "passive"))
      (node (ref "R105") (pin "2") (pinfunction "2_2") (pintype "passive"))
      (node (ref "R106") (pin "2") (pinfunction "2_2") (pintype "passive"))
      (node (ref "R107") (pin "2") (pinfunction "2_2") (pintype "passive"))
      (node (ref "TP311") (pin "1") (pinfunction "1_1") (pintype "passive"))
    )
    (net (code "52") (name "Net-(D16-K)") (class "Default")
      (node (ref "C30") (pin "1") (pinfunction "1_1") (pintype "passive"))
      (node (ref "D16") (pin "2") (pinfunction "K_2") (pintype "passive"))
      (node (ref "L2") (pin "1") (pinfunction "1_1") (pintype "passive"))
      (node (ref "TP310") (pin "1") (pinfunction "1_1") (pintype "passive"))
      (node (ref "U6") (pin "12") (pinfunction "LX_12") (pintype "passive"))
    )
    (net (code "53") (name "Net-(D100-A)") (class "Default")
      (node (ref "D100") (pin "1") (pinfunction "A_1") (pintype "passive"))
      (node (ref "J34") (pin "2") (pinfunction "2_2") (pintype "passive"))
      (node (ref "T100") (pin "3") (pinfunction "COLLECTOR_3") (pintype "passive"))
      (node (ref "TP101") (pin "1") (pinfunction "1_1") (pintype "passive"))
    )
    (net (code "54") (name "Net-(J16-Pad2)") (class "Default")
      (node (ref "J16") (pin "2") (pinfunction "2_2") (pintype "passive"))
      (node (ref "J17") (pin "1") (pinfunction "1_1") (pintype "passive"))
      (node (ref "TP19") (pin "1") (pinfunction "1_1") (pintype "passive"))
    )
    (net (code "55") (name "Net-(J17-Pad2)") (class "Default")
      (node (ref "J17") (pin "2") (pinfunction "2_2") (pintype "passive"))
      (node (ref "R47") (pin "1") (pinfunction "1_1") (pintype "passive"))
      (node (ref "R48") (pin "2") (pinfunction "2_2") (pintype "passive"))
      (node (ref "TP20") (pin "1") (pinfunction "1_1") (pintype "passive"))
    )
    (net (code "56") (name "Net-(Q1-G)") (class "Default")
      (node (ref "Q1") (pin "4") (pinfunction "G_4") (pintype "passive"))
      (node (ref "R54") (pin "2") (pinfunction "2_2") (pintype "passive"))
      (node (ref "R57") (pin "1") (pinfunction "1_1") (pintype "passive"))
      (node (ref "TP317") (pin "1") (pinfunction "1_1") (pintype "passive"))
    )
    (net (code "57") (name "Net-(Q2-G)") (class "Default")
      (node (ref "Q2") (pin "4") (pinfunction "G_4") (pintype "passive"))
      (node (ref "R55") (pin "2") (pinfunction "2_2") (pintype "passive"))
      (node (ref "R58") (pin "1") (pinfunction "1_1") (pintype "passive"))
      (node (ref "TP319") (pin "1") (pinfunction "1_1") (pintype "passive"))
    )
    (net (code "58") (name "Net-(Q3-G)") (class "Default")
      (node (ref "Q3") (pin "4") (pinfunction "G_4") (pintype "passive"))
      (node (ref "R56") (pin "2") (pinfunction "2_2") (pintype "passive"))
      (node (ref "R59") (pin "1") (pinfunction "1_1") (pintype "passive"))
      (node (ref "TP321") (pin "1") (pinfunction "1_1") (pintype "passive"))
    )
    (net (code "59") (name "Net-(T3-B)") (class "Default")
      (node (ref "R109") (pin "2") (pinfunction "2_2") (pintype "passive"))
      (node (ref "T3") (pin "1") (pinfunction "B_1") (pintype "passive"))
      (node (ref "TP303") (pin "1") (pinfunction "1_1") (pintype "passive"))
    )
    (net (code "60") (name "Net-(T100-BASE)") (class "Default")
      (node (ref "R120") (pin "2") (pinfunction "2_2") (pintype "passive"))
      (node (ref "T100") (pin "1") (pinfunction "BASE_1") (pintype "passive"))
      (node (ref "TP315") (pin "1") (pinfunction "1_1") (pintype "passive"))
    )
    (net (code "61") (name "Net-(U6-BOOT)") (class "Default")
      (node (ref "C30") (pin "2") (pinfunction "2_2") (pintype "passive"))
      (node (ref "TP309") (pin "1") (pinfunction "1_1") (pintype "passive"))
      (node (ref "U6") (pin "11") (pinfunction "BOOT_11") (pintype "passive"))
    )
    (net (code "62") (name "Net-(U6-FB)") (class "Default")
      (node (ref "C90") (pin "1") (pinfunction "1_1") (pintype "passive"))
      (node (ref "R108") (pin "1") (pinfunction "1_1") (pintype "passive"))
      (node (ref "R110") (pin "2") (pinfunction "2_2") (pintype "passive"))
      (node (ref "TP313") (pin "1") (pinfunction "1_1") (pintype "passive"))
      (node (ref "U6") (pin "5") (pinfunction "FB_5") (pintype "passive"))
    )
    (net (code "63") (name "Net-(U6-ISEN)") (class "Default")
      (node (ref "C88") (pin "2") (pinfunction "2_2") (pintype "passive"))
      (node (ref "R105") (pin "1") (pinfunction "1_1") (pintype "passive"))
      (node (ref "TP312") (pin "1") (pinfunction "1_1") (pintype "passive"))
      (node (ref "U6") (pin "8") (pinfunction "ISEN_8") (pintype "passive"))
    )
    (net (code "64") (name "Net-(U6-SS)") (class "Default")
      (node (ref "C114") (pin "2") (pinfunction "2_2") (pintype "passive"))
      (node (ref "TP308") (pin "1") (pinfunction "1_1") (pintype "passive"))
      (node (ref "U6") (pin "4") (pinfunction "SS_4") (pintype "passive"))
    )
    (net (code "65") (name "Net-(U6-TON)") (class "Default")
      (node (ref "R104") (pin "1") (pinfunction "1_1") (pintype "passive"))
      (node (ref "TP307") (pin "1") (pinfunction "1_1") (pintype "passive"))
      (node (ref "U6") (pin "3") (pinfunction "TON_3") (pintype "passive"))
    )
    (net (code "66") (name "Net-(U6-VIN)") (class "Default")
      (node (ref "C111") (pin "2") (pinfunction "2_2") (pintype "passive"))
      (node (ref "C112") (pin "2") (pinfunction "2_2") (pintype "passive"))
      (node (ref "C113") (pin "2") (pinfunction "2_2") (pintype "passive"))
      (node (ref "L100") (pin "2") (pinfunction "2_2") (pintype "passive"))
      (node (ref "R104") (pin "2") (pinfunction "2_2") (pintype "passive"))
      (node (ref "U6") (pin "1") (pinfunction "VIN_1") (pintype "passive"))
    )
    (net (code "67") (name "Net-(U7-CONT)") (class "Default")
      (node (ref "C33") (pin "2") (pinfunction "2_2") (pintype "passive"))
      (node (ref "TP301") (pin "1") (pinfunction "1_1") (pintype "passive"))
      (node (ref "U7") (pin "5") (pinfunction "CONT_5") (pintype "passive"))
    )
    (net (code "68") (name "Net-(U7-TR)") (class "Default")
      (node (ref "C32") (pin "2") (pinfunction "2_2") (pintype "passive"))
      (node (ref "R47") (pin "2") (pinfunction "2_2") (pintype "passive"))
      (node (ref "TP300") (pin "1") (pinfunction "1_1") (pintype "passive"))
      (node (ref "U7") (pin "2") (pinfunction "TR_2") (pintype "passive"))
    )
    (net (code "69") (name "Net-(U7-~{RESET})") (class "Default")
      (node (ref "R46") (pin "1") (pinfunction "1_1") (pintype "passive"))
      (node (ref "TP302") (pin "1") (pinfunction "1_1") (pintype "passive"))
      (node (ref "U7") (pin "4") (pinfunction "~{RESET}_4") (pintype "passive"))
    )
    (net (code "70") (name "VCC{slash}2") (class "Default")
      (node (ref "C110") (pin "2") (pinfunction "2_2") (pintype "passive"))
      (node (ref "C117") (pin "2") (pinfunction "2_2") (pintype "passive"))
      (node (ref "L100") (pin "1") (pinfunction "1_1") (pintype "passive"))
      (node (ref "R49") (pin "2") (pinfunction "2_2") (pintype "passive"))
      (node (ref "SW1") (pin "1") (pinfunction "1_1") (pintype "passive"))
    )
    (net (code "71") (name "unconnected-(K1-Pad5)") (class "Default")
      (node (ref "K1") (pin "5") (pinfunction "5_5") (pintype "passive"))
    )
    (net (code "72") (name "unconnected-(SW1-Pad3)") (class "Default")
      (node (ref "SW1") (pin "3") (pinfunction "3_3") (pintype "passive"))
    )
    (net (code "73") (name "unconnected-(U7-DIS-Pad7)") (class "Default")
      (node (ref "U7") (pin "7") (pinfunction "DIS_7") (pintype "passive"))
    )
    (net (code "74") (name "unconnected-(U9-BYPASS-Pad4)") (class "Default")
      (node (ref "U9") (pin "4") (pinfunction "BYPASS_4") (pintype "passive"))
    )
  )
)
